# AtmegaRFM69.net
KiCad netlist of a schematic drawn in EAGLE
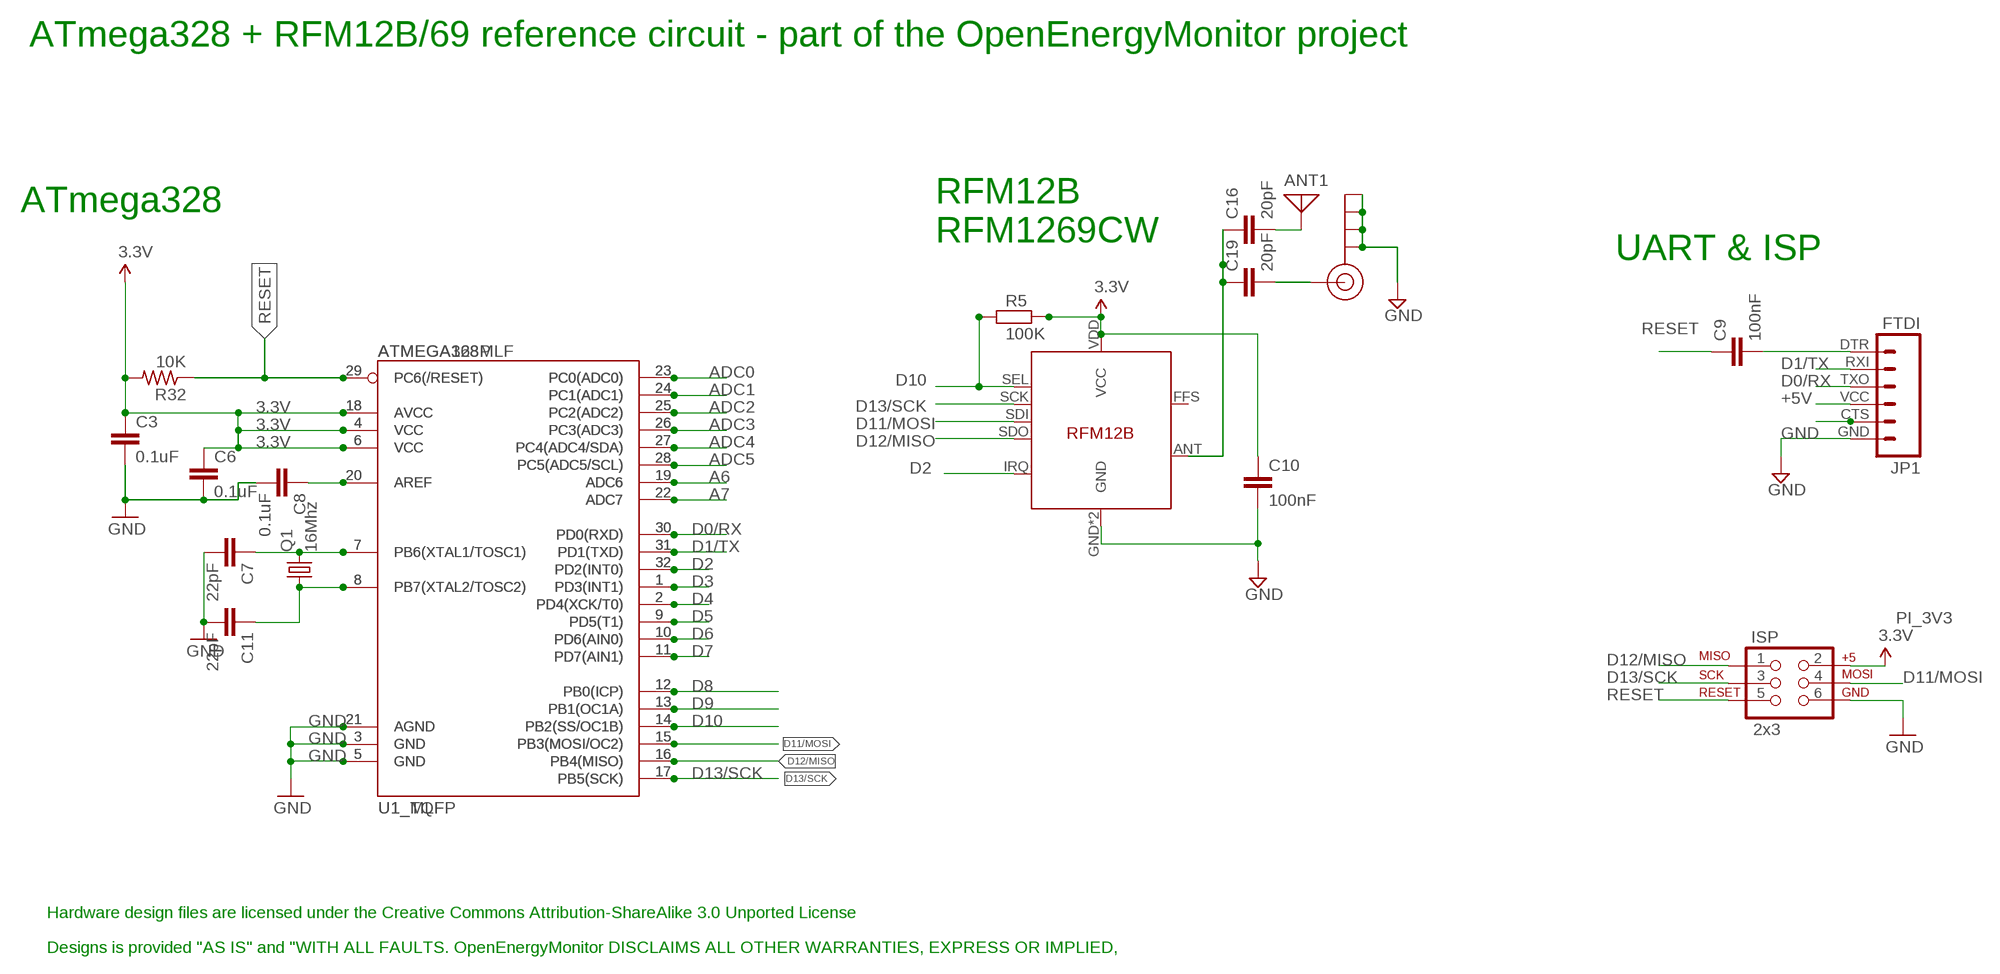
[diagram p0: schematic, sheet 1]

(export (version "E")
  (design (tool "Eeschema 10.0.6"))
  (components
    (comp (ref "ANT1")
      (value "ANTENNA")
      (footprint "eagle-import:PAD-01")
      (libsource (lib "eagle-import") (part "ANTENNA"))
    )
    (comp (ref "C3")
      (value "0.1uF")
      (footprint "eagle-import:C0603")
      (libsource (lib "eagle-import") (part "C-EUC0603"))
    )
    (comp (ref "C6")
      (value "0.1uF")
      (footprint "eagle-import:C0603")
      (libsource (lib "eagle-import") (part "resistor_C-EUC0603"))
    )
    (comp (ref "C7")
      (value "22pF")
      (footprint "eagle-import:C0603")
      (libsource (lib "eagle-import") (part "resistor_C-EUC0603"))
    )
    (comp (ref "C8")
      (value "0.1uF")
      (footprint "eagle-import:C0603")
      (libsource (lib "eagle-import") (part "resistor_C-EUC0603"))
    )
    (comp (ref "C9")
      (value "100nF")
      (footprint "eagle-import:C0603")
      (libsource (lib "eagle-import") (part "C-EUC0603"))
    )
    (comp (ref "C10")
      (value "100nF")
      (footprint "eagle-import:C0603")
      (libsource (lib "eagle-import") (part "C-EUC0603"))
    )
    (comp (ref "C11")
      (value "22pF")
      (footprint "eagle-import:C0603")
      (libsource (lib "eagle-import") (part "resistor_C-EUC0603"))
    )
    (comp (ref "C16")
      (value "20pF")
      (footprint "eagle-import:C0603")
      (libsource (lib "eagle-import") (part "C-EUC0603"))
    )
    (comp (ref "C19")
      (value "20pF")
      (footprint "eagle-import:C0603")
      (libsource (lib "eagle-import") (part "C-EUC0603"))
    )
    (comp (ref "ISP")
      (value "2x3")
      (footprint "eagle-import:2X3")
      (libsource (lib "eagle-import") (part "AVR_SPI_PRG_6PTH"))
    )
    (comp (ref "J$1")
      (value "SMA_EDGE")
      (footprint "eagle-import:SMA-EDGE")
      (libsource (lib "eagle-import") (part "SMA_EDGE"))
    )
    (comp (ref "JP1")
      (value "FTDI")
      (footprint "eagle-import:FTDI_BASIC")
      (libsource (lib "eagle-import") (part "FTDI_BASICPTH"))
    )
    (comp (ref "Q1")
      (value "16Mhz")
      (footprint "eagle-import:HC49UP")
      (libsource (lib "eagle-import") (part "CRYSTALHC49UP"))
    )
    (comp (ref "R5")
      (value "100K")
      (footprint "eagle-import:R0603")
      (libsource (lib "eagle-import") (part "R-EU_R0603"))
    )
    (comp (ref "R32")
      (value "10K")
      (footprint "eagle-import:R0603")
      (libsource (lib "eagle-import") (part "R-US_R0603"))
    )
    (comp (ref "U$14")
      (value "RFM12B")
      (footprint "eagle-import:RFM12B")
      (libsource (lib "eagle-import") (part "RFM12B"))
    )
    (comp (ref "U1_MLF")
      (value "ATMEGA168MLF")
      (footprint "eagle-import:MLF32")
      (libsource (lib "eagle-import") (part "ATMEGA168MLF"))
    )
    (comp (ref "U1_TQFP")
      (value "ATMEGA328P")
      (footprint "eagle-import:TQFP32-08")
      (libsource (lib "eagle-import") (part "ATMEGA328_SMT"))
    )
  )
  (nets
    (net (code "1") (name "/+5V") (class "Default")
      (node (ref "JP1") (pin "VCC") (pinfunction "4_VCC") (pintype "passive"))
    )
    (net (code "2") (name "/A6") (class "Default")
      (node (ref "U1_MLF") (pin "19") (pinfunction "ADC6_19") (pintype "bidirectional"))
      (node (ref "U1_TQFP") (pin "19") (pinfunction "ADC6_19") (pintype "bidirectional"))
    )
    (net (code "3") (name "/A7") (class "Default")
      (node (ref "U1_MLF") (pin "22") (pinfunction "ADC7_22") (pintype "bidirectional"))
      (node (ref "U1_TQFP") (pin "22") (pinfunction "ADC7_22") (pintype "bidirectional"))
    )
    (net (code "4") (name "/ADC0") (class "Default")
      (node (ref "U1_MLF") (pin "23") (pinfunction "PC0(ADC0)_23") (pintype "bidirectional"))
      (node (ref "U1_TQFP") (pin "23") (pinfunction "PC0(ADC0)_23") (pintype "bidirectional"))
    )
    (net (code "5") (name "/ADC1") (class "Default")
      (node (ref "U1_MLF") (pin "24") (pinfunction "PC1(ADC1)_24") (pintype "bidirectional"))
      (node (ref "U1_TQFP") (pin "24") (pinfunction "PC1(ADC1)_24") (pintype "bidirectional"))
    )
    (net (code "6") (name "/ADC2") (class "Default")
      (node (ref "U1_MLF") (pin "25") (pinfunction "PC2(ADC2)_25") (pintype "bidirectional"))
      (node (ref "U1_TQFP") (pin "25") (pinfunction "PC2(ADC2)_25") (pintype "bidirectional"))
    )
    (net (code "7") (name "/ADC3") (class "Default")
      (node (ref "U1_MLF") (pin "26") (pinfunction "PC3(ADC3)_26") (pintype "bidirectional"))
      (node (ref "U1_TQFP") (pin "26") (pinfunction "PC3(ADC3)_26") (pintype "bidirectional"))
    )
    (net (code "8") (name "/ADC4") (class "Default")
      (node (ref "U1_MLF") (pin "27") (pinfunction "PC4(ADC4/SDA)_27") (pintype "bidirectional"))
      (node (ref "U1_TQFP") (pin "27") (pinfunction "PC4(ADC4/SDA)_27") (pintype "bidirectional"))
    )
    (net (code "9") (name "/ADC5") (class "Default")
      (node (ref "U1_MLF") (pin "28") (pinfunction "PC5(ADC5/SCL)_28") (pintype "bidirectional"))
      (node (ref "U1_TQFP") (pin "28") (pinfunction "PC5(ADC5/SCL)_28") (pintype "bidirectional"))
    )
    (net (code "10") (name "/D0{slash}RX") (class "Default")
      (node (ref "JP1") (pin "TXO") (pinfunction "3_TXO") (pintype "passive"))
      (node (ref "U1_MLF") (pin "30") (pinfunction "PD0(RXD)_30") (pintype "bidirectional"))
      (node (ref "U1_TQFP") (pin "30") (pinfunction "PD0(RXD)_30") (pintype "bidirectional"))
    )
    (net (code "11") (name "/D1{slash}TX") (class "Default")
      (node (ref "JP1") (pin "RXI") (pinfunction "2_RXI") (pintype "passive"))
      (node (ref "U1_MLF") (pin "31") (pinfunction "PD1(TXD)_31") (pintype "bidirectional"))
      (node (ref "U1_TQFP") (pin "31") (pinfunction "PD1(TXD)_31") (pintype "bidirectional"))
    )
    (net (code "12") (name "/D2") (class "Default")
      (node (ref "U$14") (pin "IRQ") (pinfunction "IRQ_IRQ") (pintype "open_collector"))
      (node (ref "U1_MLF") (pin "32") (pinfunction "PD2(INT0)_32") (pintype "bidirectional"))
      (node (ref "U1_TQFP") (pin "32") (pinfunction "PD2(INT0)_32") (pintype "bidirectional"))
    )
    (net (code "13") (name "/D3") (class "Default")
      (node (ref "U1_MLF") (pin "1") (pinfunction "PD3(INT1)_1") (pintype "bidirectional"))
      (node (ref "U1_TQFP") (pin "1") (pinfunction "PD3(INT1)_1") (pintype "bidirectional"))
    )
    (net (code "14") (name "/D4") (class "Default")
      (node (ref "U1_MLF") (pin "2") (pinfunction "PD4(XCK/T0)_2") (pintype "bidirectional"))
      (node (ref "U1_TQFP") (pin "2") (pinfunction "PD4(XCK/T0)_2") (pintype "bidirectional"))
    )
    (net (code "15") (name "/D5") (class "Default")
      (node (ref "U1_MLF") (pin "9") (pinfunction "PD5(T1)_9") (pintype "bidirectional"))
      (node (ref "U1_TQFP") (pin "9") (pinfunction "PD5(T1)_9") (pintype "bidirectional"))
    )
    (net (code "16") (name "/D6") (class "Default")
      (node (ref "U1_MLF") (pin "10") (pinfunction "PD6(AIN0)_10") (pintype "bidirectional"))
      (node (ref "U1_TQFP") (pin "10") (pinfunction "PD6(AIN0)_10") (pintype "bidirectional"))
    )
    (net (code "17") (name "/D7") (class "Default")
      (node (ref "U1_MLF") (pin "11") (pinfunction "PD7(AIN1)_11") (pintype "bidirectional"))
      (node (ref "U1_TQFP") (pin "11") (pinfunction "PD7(AIN1)_11") (pintype "bidirectional"))
    )
    (net (code "18") (name "/D8") (class "Default")
      (node (ref "U1_MLF") (pin "12") (pinfunction "PB0(ICP)_12") (pintype "bidirectional"))
      (node (ref "U1_TQFP") (pin "12") (pinfunction "PB0(ICP)_12") (pintype "bidirectional"))
    )
    (net (code "19") (name "/D9") (class "Default")
      (node (ref "U1_MLF") (pin "13") (pinfunction "PB1(OC1A)_13") (pintype "bidirectional"))
      (node (ref "U1_TQFP") (pin "13") (pinfunction "PB1(OC1A)_13") (pintype "bidirectional"))
    )
    (net (code "20") (name "/D10") (class "Default")
      (node (ref "R5") (pin "1") (pinfunction "1_1") (pintype "passive"))
      (node (ref "U$14") (pin "SEL") (pinfunction "SEL_SEL") (pintype "input"))
      (node (ref "U1_MLF") (pin "14") (pinfunction "PB2(SS/OC1B)_14") (pintype "bidirectional"))
      (node (ref "U1_TQFP") (pin "14") (pinfunction "PB2(SS/OC1B)_14") (pintype "bidirectional"))
    )
    (net (code "22") (name "3.3V") (class "Default")
      (node (ref "C10") (pin "1") (pinfunction "1_1") (pintype "passive"))
      (node (ref "C3") (pin "1") (pinfunction "1_1") (pintype "passive"))
      (node (ref "C6") (pin "1") (pinfunction "1_1") (pintype "passive"))
      (node (ref "ISP") (pin "2") (pinfunction "2_2") (pintype "passive"))
      (node (ref "R32") (pin "2") (pinfunction "2_2") (pintype "passive"))
      (node (ref "R5") (pin "2") (pinfunction "2_2") (pintype "passive"))
      (node (ref "U$14") (pin "VDD") (pinfunction "VCC_VDD") (pintype "power_in"))
      (node (ref "U1_MLF") (pin "18") (pinfunction "AVCC_18") (pintype "bidirectional"))
      (node (ref "U1_MLF") (pin "4") (pinfunction "VCC_4") (pintype "bidirectional"))
      (node (ref "U1_MLF") (pin "6") (pinfunction "VCC_6") (pintype "bidirectional"))
      (node (ref "U1_TQFP") (pin "18") (pinfunction "AVCC_18") (pintype "bidirectional"))
      (node (ref "U1_TQFP") (pin "4") (pinfunction "VCC_4") (pintype "bidirectional"))
      (node (ref "U1_TQFP") (pin "6") (pinfunction "VCC_6") (pintype "bidirectional"))
    )
    (net (code "23") (name "D11{slash}MOSI") (class "Default")
      (node (ref "ISP") (pin "4") (pinfunction "4_4") (pintype "passive"))
      (node (ref "U$14") (pin "SDI") (pinfunction "SDI_SDI") (pintype "input"))
      (node (ref "U1_MLF") (pin "15") (pinfunction "PB3(MOSI/OC2)_15") (pintype "bidirectional"))
      (node (ref "U1_TQFP") (pin "15") (pinfunction "PB3(MOSI/OC2)_15") (pintype "bidirectional"))
    )
    (net (code "24") (name "D12{slash}MISO") (class "Default")
      (node (ref "ISP") (pin "1") (pinfunction "1_1") (pintype "passive"))
      (node (ref "U$14") (pin "SDO") (pinfunction "SDO_SDO") (pintype "output"))
      (node (ref "U1_MLF") (pin "16") (pinfunction "PB4(MISO)_16") (pintype "bidirectional"))
      (node (ref "U1_TQFP") (pin "16") (pinfunction "PB4(MISO)_16") (pintype "bidirectional"))
    )
    (net (code "25") (name "D13{slash}SCK") (class "Default")
      (node (ref "ISP") (pin "3") (pinfunction "3_3") (pintype "passive"))
      (node (ref "U$14") (pin "SCK") (pinfunction "SCK_SCK") (pintype "input"))
      (node (ref "U1_MLF") (pin "17") (pinfunction "PB5(SCK)_17") (pintype "bidirectional"))
      (node (ref "U1_TQFP") (pin "17") (pinfunction "PB5(SCK)_17") (pintype "bidirectional"))
    )
    (net (code "26") (name "GND") (class "Default")
      (node (ref "C10") (pin "2") (pinfunction "2_2") (pintype "passive"))
      (node (ref "C11") (pin "2") (pinfunction "2_2") (pintype "passive"))
      (node (ref "C3") (pin "2") (pinfunction "2_2") (pintype "passive"))
      (node (ref "C6") (pin "2") (pinfunction "2_2") (pintype "passive"))
      (node (ref "C7") (pin "2") (pinfunction "2_2") (pintype "passive"))
      (node (ref "C8") (pin "2") (pinfunction "2_2") (pintype "passive"))
      (node (ref "ISP") (pin "6") (pinfunction "6_6") (pintype "passive"))
      (node (ref "J$1") (pin "GND@0") (pinfunction "GND_GND@0") (pintype "bidirectional"))
      (node (ref "J$1") (pin "GND@1") (pinfunction "GND_GND@1") (pintype "bidirectional"))
      (node (ref "J$1") (pin "GND@2") (pinfunction "GND_GND@2") (pintype "bidirectional"))
      (node (ref "J$1") (pin "GND@3") (pinfunction "GND_GND@3") (pintype "bidirectional"))
      (node (ref "JP1") (pin "GND") (pinfunction "6_GND") (pintype "passive"))
      (node (ref "U$14") (pin "GND") (pinfunction "GND_GND") (pintype "power_in"))
      (node (ref "U$14") (pin "P$12") (pinfunction "GND_P$12") (pintype "power_in"))
      (node (ref "U1_MLF") (pin "21") (pinfunction "AGND_21") (pintype "bidirectional"))
      (node (ref "U1_MLF") (pin "3") (pinfunction "GND_3") (pintype "bidirectional"))
      (node (ref "U1_MLF") (pin "5") (pinfunction "GND_5") (pintype "bidirectional"))
      (node (ref "U1_TQFP") (pin "21") (pinfunction "AGND_21") (pintype "bidirectional"))
      (node (ref "U1_TQFP") (pin "3") (pinfunction "GND_3") (pintype "bidirectional"))
      (node (ref "U1_TQFP") (pin "5") (pinfunction "GND_5") (pintype "bidirectional"))
    )
    (net (code "27") (name "Net-(ANT1-Pad1)") (class "Default")
      (node (ref "ANT1") (pin "1") (pinfunction "1_1") (pintype "output"))
      (node (ref "C16") (pin "2") (pinfunction "2_2") (pintype "passive"))
    )
    (net (code "28") (name "Net-(C16-Pad1)") (class "Default")
      (node (ref "C16") (pin "1") (pinfunction "1_1") (pintype "passive"))
      (node (ref "C19") (pin "1") (pinfunction "1_1") (pintype "passive"))
      (node (ref "U$14") (pin "ANT") (pinfunction "ANT_ANT") (pintype "passive"))
    )
    (net (code "29") (name "Net-(J$1-SIGNAL)") (class "Default")
      (node (ref "C19") (pin "2") (pinfunction "2_2") (pintype "passive"))
      (node (ref "J$1") (pin "SIG") (pinfunction "SIGNAL_SIG") (pintype "bidirectional"))
    )
    (net (code "30") (name "Net-(JP1-1)") (class "Default")
      (node (ref "C9") (pin "2") (pinfunction "2_2") (pintype "passive"))
      (node (ref "JP1") (pin "DTR") (pinfunction "1_DTR") (pintype "passive"))
    )
    (net (code "31") (name "Net-(U1_MLF-AREF)") (class "Default")
      (node (ref "C8") (pin "1") (pinfunction "1_1") (pintype "passive"))
      (node (ref "U1_MLF") (pin "20") (pinfunction "AREF_20") (pintype "bidirectional"))
      (node (ref "U1_TQFP") (pin "20") (pinfunction "AREF_20") (pintype "bidirectional"))
    )
    (net (code "32") (name "Net-(U1_MLF-PB6(XTAL1{slash}TOSC1))") (class "Default")
      (node (ref "C7") (pin "1") (pinfunction "1_1") (pintype "passive"))
      (node (ref "Q1") (pin "2") (pinfunction "2_2") (pintype "passive"))
      (node (ref "U1_MLF") (pin "7") (pinfunction "PB6(XTAL1/TOSC1)_7") (pintype "bidirectional"))
      (node (ref "U1_TQFP") (pin "7") (pinfunction "PB6(XTAL1/TOSC1)_7") (pintype "bidirectional"))
    )
    (net (code "33") (name "Net-(U1_MLF-PB7(XTAL2{slash}TOSC2))") (class "Default")
      (node (ref "C11") (pin "1") (pinfunction "1_1") (pintype "passive"))
      (node (ref "Q1") (pin "1") (pinfunction "1_1") (pintype "passive"))
      (node (ref "U1_MLF") (pin "8") (pinfunction "PB7(XTAL2/TOSC2)_8") (pintype "bidirectional"))
      (node (ref "U1_TQFP") (pin "8") (pinfunction "PB7(XTAL2/TOSC2)_8") (pintype "bidirectional"))
    )
    (net (code "34") (name "RESET") (class "Default")
      (node (ref "C9") (pin "1") (pinfunction "1_1") (pintype "passive"))
      (node (ref "ISP") (pin "5") (pinfunction "5_5") (pintype "passive"))
      (node (ref "R32") (pin "1") (pinfunction "1_1") (pintype "passive"))
      (node (ref "U1_MLF") (pin "29") (pinfunction "PC6(/RESET)_29") (pintype "bidirectional"))
      (node (ref "U1_TQFP") (pin "29") (pinfunction "PC6(/RESET)_29") (pintype "bidirectional"))
    )
    (net (code "35") (name "unconnected-(JP1-5-PadCTS)") (class "Default")
      (node (ref "JP1") (pin "CTS") (pinfunction "5_CTS") (pintype "passive"))
    )
    (net (code "36") (name "unconnected-(U$14-PadFFS)") (class "Default")
      (node (ref "U$14") (pin "FFS") (pinfunction "FFS_FFS") (pintype "bidirectional"))
    )
  )
)
